# BSR033A.net
KiCad netlist of a schematic drawn in Altium Designer
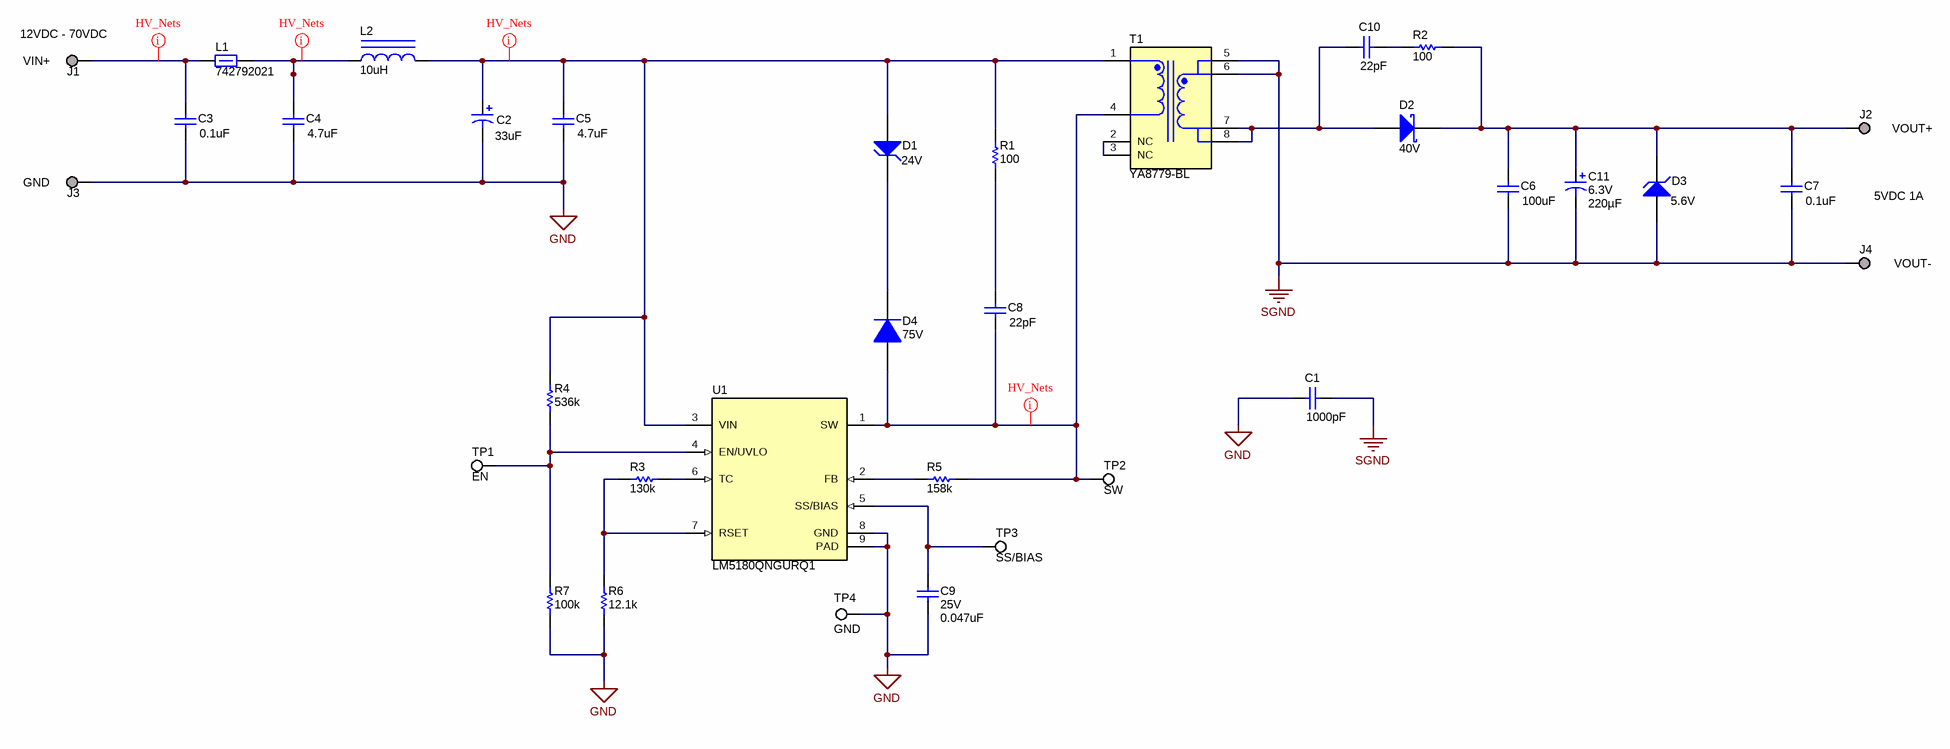
[diagram p0: BSR033A.SchDoc]

(export (version "E")
  (design (tool "Eeschema 10.0.6"))
  (components
    (comp (ref "C1")
      (value "202R18W102KV4E")
      (footprint "1206_190")
      (description "CAP, CERM, 1000 pF, 2000 V, +/- 10%, X7R, 1206_190")
      (fields
        (field (name "MANUFACTURER") "Johanson Technology")
        (field (name "VALUEDISPLAYED") "1000pF")
        (field (name "PUBLISHER") "Texas Instruments")
      )
      (libsource (lib "Altium Vault - TI") (part "CMP-0008572-2"))
    )
    (comp (ref "C2")
      (value "EEE-FK2A330P")
      (footprint "SM_RADIAL_G")
      (description "CAP, AL, 33 uF, 100 V, +/- 20%, 0.7 ohm, AEC-Q200 Grade 2, SMD")
      (fields
        (field (name "MANUFACTURER") "Panasonic")
        (field (name "VALUEDISPLAYED") "33uF")
        (field (name "PUBLISHER") "Texas Instruments")
      )
      (libsource (lib "Altium Vault - TI") (part "CMP-0011203-2"))
    )
    (comp (ref "C3")
      (value "GRM188R72A104KA35J")
      (footprint "0603L")
      (description "CAP, CERM, 0.1 uF, 100 V, +/- 10%, X7R, 0603")
      (fields
        (field (name "MANUFACTURER") "MuRata")
        (field (name "VALUEDISPLAYED") "0.1uF")
        (field (name "PUBLISHER") "Texas Instruments")
      )
      (libsource (lib "Altium Vault - TI") (part "CMP-0007470-5"))
    )
    (comp (ref "C4")
      (value "GRM32DC72A475KE01L")
      (footprint "1210_220")
      (description "CAP, CERM, 4.7 uF, 100 V, +/- 10%, X7S, 1210")
      (fields
        (field (name "MANUFACTURER") "MuRata")
        (field (name "VALUEDISPLAYED") "4.7uF")
        (field (name "PUBLISHER") "Texas Instruments")
      )
      (libsource (lib "Altium Vault - TI") (part "CMP-0009182-2"))
    )
    (comp (ref "C5")
      (value "GRM32DC72A475KE01L")
      (footprint "1210_220")
      (description "CAP, CERM, 4.7 uF, 100 V, +/- 10%, X7S, 1210")
      (fields
        (field (name "MANUFACTURER") "MuRata")
        (field (name "VALUEDISPLAYED") "4.7uF")
        (field (name "PUBLISHER") "Texas Instruments")
      )
      (libsource (lib "Altium Vault - TI") (part "CMP-0009182-2"))
    )
    (comp (ref "C6")
      (value "GRM32EC80J107ME20L")
      (footprint "1210_270")
      (description "CAP, CERM, 100 uF, 6.3 V, +/- 20%, X6S, 1210")
      (fields
        (field (name "MANUFACTURER") "MuRata")
        (field (name "VALUEDISPLAYED") "100uF")
        (field (name "PUBLISHER") "Texas Instruments")
      )
      (libsource (lib "Altium Vault - TI") (part "Capacitor"))
    )
    (comp (ref "C7")
      (value "GRM188R72A104KA35J")
      (footprint "0603L")
      (description "CAP, CERM, 0.1 uF, 100 V, +/- 10%, X7R, 0603")
      (fields
        (field (name "MANUFACTURER") "MuRata")
        (field (name "VALUEDISPLAYED") "0.1uF")
        (field (name "PUBLISHER") "Texas Instruments")
      )
      (libsource (lib "Altium Vault - TI") (part "CMP-0007470-5"))
    )
    (comp (ref "C8")
      (value "GRM1885C2A220JA01D")
      (footprint "0603_HV")
      (description "CAP, CERM, 22 pF, 100 V, +/- 5%, C0G/NP0, 0603")
      (fields
        (field (name "MANUFACTURER") "MuRata")
        (field (name "VALUEDISPLAYED") "22pF")
        (field (name "PUBLISHER") "Texas Instruments")
      )
      (libsource (lib "Altium Vault - TI") (part "CMP-0007255-4"))
    )
    (comp (ref "C9")
      (value "GCM188R71E473KA37D")
      (footprint "0603L")
      (description "CAP, CERM, 0.047 uF, 25 V, +/- 10%, X7R, AEC-Q200 Grade 1, 0603")
      (fields
        (field (name "MANUFACTURER") "MuRata")
        (field (name "VDC_V") "25V")
        (field (name "VALUEDISPLAYED") "0.047uF")
        (field (name "PUBLISHER") "Texas Instruments")
      )
      (libsource (lib "Altium Vault - TI") (part "CMP-0007141-5"))
    )
    (comp (ref "C10")
      (value "GRM1885C2A220JA01D")
      (footprint "0603_HV")
      (description "CAP, CERM, 22 pF, 100 V, +/- 5%, C0G/NP0, 0603")
      (fields
        (field (name "MANUFACTURER") "MuRata")
        (field (name "VALUEDISPLAYED") "22pF")
        (field (name "PUBLISHER") "Texas Instruments")
      )
      (libsource (lib "Altium Vault - TI") (part "CMP-0007255-4"))
    )
    (comp (ref "C11")
      (value "T598D107M010ATE025")
      (footprint "7343-31")
      (description "CAP, Aluminum Polymer, 220 µF, 6.3 V,+/- 20%, 0.01 ohm, 7343-31 SMD")
      (fields
        (field (name "MANUFACTURER") "MuRata")
        (field (name "PARTNUMBER") "ECASD60J227M010K00")
        (field (name "VDC_V") "6.3V")
        (field (name "VALUEDISPLAYED") "220µF")
      )
      (libsource (lib "Altium Vault - TI") (part "Cap_Polarized"))
    )
    (comp (ref "D1")
      (value "DFLZ24-7")
      (footprint "PowerDI123")
      (description "Diode, Zener, 24 V, 1 W, PowerDI123")
      (fields
        (field (name "VZ_V") "24V")
        (field (name "MANUFACTURER") "Diodes Inc.")
        (field (name "PUBLISHER") "Texas Instruments")
      )
      (libsource (lib "Altium Vault - TI") (part "CMP-0005415-2"))
    )
    (comp (ref "D2")
      (value "40V")
      (footprint "SMAF")
      (description "Diode, Schottky, 40 V, 3 A, AEC-Q101, SMAF")
      (fields
        (field (name "PARTNUMBER") "FSV340AF")
        (field (name "MANUFACTURER") "Fairchild Semiconductor")
        (field (name "PUBLISHER") "Texas Instruments")
      )
      (libsource (lib "Altium Vault - TI") (part "CMP-0028855-1"))
    )
    (comp (ref "D3")
      (value "MMSZ5232BS-7-F")
      (footprint "SOD-323")
      (description "Diode, Zener, 5.6 V, 200 mW, SOD-323")
      (fields
        (field (name "VZ_V") "5.6V")
        (field (name "MANUFACTURER") "Diodes Inc.")
        (field (name "PUBLISHER") "Texas Instruments")
      )
      (libsource (lib "Altium Vault - TI") (part "CMP-0005855-1"))
    )
    (comp (ref "D4")
      (value "75V")
      (footprint "SOD-323")
      (description "Diode, Ultrafast, 75 V, 0.25 A, SOD-323")
      (fields
        (field (name "MANUFACTURER") "Central Semiconductor")
        (field (name "PARTNUMBER") "CMDD4448")
        (field (name "PUBLISHER") "Texas Instruments")
      )
      (libsource (lib "Altium Vault - TI") (part "CMP-0029019-1"))
    )
    (comp (ref "J1")
      (value "1573-2")
      (footprint "Keystone1573-2")
      (description "Terminal, Turret, TH, Double")
      (fields (field (name "MANUFACTURER") "Keystone") (field (name "PUBLISHER") "Texas Instruments"))
      (libsource (lib "Altium Vault - TI") (part "CMP-0055119-1"))
    )
    (comp (ref "J2")
      (value "1573-2")
      (footprint "Keystone1573-2")
      (description "Terminal, Turret, TH, Double")
      (fields (field (name "MANUFACTURER") "Keystone") (field (name "PUBLISHER") "Texas Instruments"))
      (libsource (lib "Altium Vault - TI") (part "CMP-0055119-1"))
    )
    (comp (ref "J3")
      (value "1573-2")
      (footprint "Keystone1573-2")
      (description "Terminal, Turret, TH, Double")
      (fields (field (name "MANUFACTURER") "Keystone") (field (name "PUBLISHER") "Texas Instruments"))
      (libsource (lib "Altium Vault - TI") (part "Turret"))
    )
    (comp (ref "J4")
      (value "1573-2")
      (footprint "Keystone1573-2")
      (description "Terminal, Turret, TH, Double")
      (fields (field (name "MANUFACTURER") "Keystone") (field (name "PUBLISHER") "Texas Instruments"))
      (libsource (lib "Altium Vault - TI") (part "Turret"))
    )
    (comp (ref "L1")
      (value "742792021")
      (footprint "0805_HV")
      (description "Ferrite Bead, 22 ohm @ 100 MHz, 6 A, 0805")
      (fields (field (name "MANUFACTURER") "Wurth Elektronik") (field (name "PUBLISHER") "Texas Instruments"))
      (libsource (lib "Altium Vault - TI") (part "Ferrite_Bead"))
    )
    (comp (ref "L2")
      (value "744042100")
      (footprint "WE-TPC-M1")
      (description "Inductor, Shielded Drum Core, Ferrite, 10 uH, 1 A, 0.12 ohm, SMD")
      (fields
        (field (name "MANUFACTURER") "Wurth Elektronik")
        (field (name "VALUEDISPLAYED") "10uH")
        (field (name "PUBLISHER") "Texas Instruments")
      )
      (libsource (lib "Altium Vault - TI") (part "CMP-0063804-1"))
    )
    (comp (ref "R1")
      (value "CRCW0603100RFKEA")
      (footprint "0603L")
      (description "RES, 100, 1%, 0.1 W, 0603")
      (fields
        (field (name "MANUFACTURER") "Vishay-Dale")
        (field (name "VALUEDISPLAYED") "100")
        (field (name "PUBLISHER") "Texas Instruments")
      )
      (libsource (lib "Altium Vault - TI") (part "CMP-0021991-3"))
    )
    (comp (ref "R2")
      (value "CRCW0603100RFKEA")
      (footprint "0603L")
      (description "RES, 100, 1%, 0.1 W, 0603")
      (fields
        (field (name "MANUFACTURER") "Vishay-Dale")
        (field (name "VALUEDISPLAYED") "100")
        (field (name "PUBLISHER") "Texas Instruments")
      )
      (libsource (lib "Altium Vault - TI") (part "CMP-0021991-3"))
    )
    (comp (ref "R3")
      (value "CRCW0603130KFKEA")
      (footprint "0603L")
      (description "RES, 130 k, 1%, 0.1 W, AEC-Q200 Grade 0, 0603")
      (fields (field (name "MANUFACTURER") "Vishay-Dale") (field (name "VALUEDISPLAYED") "130k"))
      (libsource (lib "Altium Vault - TI") (part "CMP-0022036-4"))
    )
    (comp (ref "R4")
      (value "CRCW0603536KFKEA")
      (footprint "0603_HV")
      (description "RES, 536 k, 1%, 0.1 W, AEC-Q200 Grade 0, 0603")
      (fields (field (name "MANUFACTURER") "Vishay-Dale") (field (name "VALUEDISPLAYED") "536k"))
      (libsource (lib "Altium Vault - TI") (part "CMP-0022488-4"))
    )
    (comp (ref "R5")
      (value "CRCW0603158KFKEA")
      (footprint "0603_HV")
      (description "RES, 158 k, 1%, 0.1 W, AEC-Q200 Grade 0, 0603")
      (fields (field (name "MANUFACTURER") "Vishay-Dale") (field (name "VALUEDISPLAYED") "158k"))
      (libsource (lib "Altium Vault - TI") (part "CMP-0022064-4"))
    )
    (comp (ref "R6")
      (value "CRCW060312K1FKEA")
      (footprint "0603L")
      (description "RES, 12.1 k, 1%, 0.1 W, 0603")
      (fields
        (field (name "MANUFACTURER") "Vishay-Dale")
        (field (name "VALUEDISPLAYED") "12.1k")
        (field (name "PUBLISHER") "Texas Instruments")
      )
      (libsource (lib "Altium Vault - TI") (part "CMP-0022030-3"))
    )
    (comp (ref "R7")
      (value "CRCW0603100KFKEA")
      (footprint "0603L")
      (description "RES, 100 k, 1%, 0.1 W, AEC-Q200 Grade 0, 0603")
      (fields (field (name "MANUFACTURER") "Vishay-Dale") (field (name "VALUEDISPLAYED") "100k"))
      (libsource (lib "Altium Vault - TI") (part "CMP-0021990-4"))
    )
    (comp (ref "T1")
      (value "YA8779-BL")
      (footprint "Coilcraft_YA8779-CL")
      (description "Transformer, 30 uH, SMD")
      (fields (field (name "MANUFACTURER") "Coilcraft"))
      (libsource (lib "Altium Vault - TI") (part "Coilcraft_YA8779-CL"))
    )
    (comp (ref "TP1")
      (value "EN")
      (footprint "Testpoint_Keystone_Miniature")
      (description "Test Point, Miniature, SMT")
      (fields
        (field (name "MANUFACTURER") "Keystone")
        (field (name "PARTNUMBER") "5015")
        (field (name "PUBLISHER") "Texas Instruments")
      )
      (libsource (lib "Altium Vault - TI") (part "CMP-0055152-1"))
    )
    (comp (ref "TP2")
      (value "SW")
      (footprint "Testpoint_Keystone_Miniature")
      (description "Test Point, Miniature, SMT")
      (fields
        (field (name "MANUFACTURER") "Keystone")
        (field (name "PARTNUMBER") "5015")
        (field (name "PUBLISHER") "Texas Instruments")
      )
      (libsource (lib "Altium Vault - TI") (part "CMP-0055152-1"))
    )
    (comp (ref "TP3")
      (value "SS/BIAS")
      (footprint "Testpoint_Keystone_Miniature")
      (description "Test Point, Miniature, SMT")
      (fields
        (field (name "MANUFACTURER") "Keystone")
        (field (name "PARTNUMBER") "5015")
        (field (name "PUBLISHER") "Texas Instruments")
      )
      (libsource (lib "Altium Vault - TI") (part "CMP-0055152-1"))
    )
    (comp (ref "TP4")
      (value "GND")
      (footprint "Testpoint_Keystone_Miniature")
      (description "Test Point, Miniature, SMT")
      (fields
        (field (name "MANUFACTURER") "Keystone")
        (field (name "PARTNUMBER") "5015")
        (field (name "PUBLISHER") "Texas Instruments")
      )
      (libsource (lib "Altium Vault - TI") (part "CMP-0055152-1"))
    )
    (comp (ref "U1")
      (value "LM5180QNGURQ1")
      (footprint "NGU0008C")
      (description "70-V PSR Flyback Converter With 100-V, 1.2-A Power Switch and Ultra-Low IQ, NGU0008C (WSON-8)")
      (fields
        (field (name "ALTERNATE PARTNUMBER") "LM5180QNGUTQ1")
        (field (name "MANUFACTURER") "Texas Instruments")
        (field (name "PARTNUMBER") "LM5180QNGURQ1")
      )
      (libsource (lib "Altium Vault - TI") (part "LM5180-Q1"))
    )
  )
  (nets
    (net (code "1") (name "GND") (class "Default")
      (node (ref "C1") (pin "2") (pinfunction "2_2") (pintype "passive"))
      (node (ref "C2") (pin "2") (pinfunction "-_2") (pintype "passive"))
      (node (ref "C3") (pin "2") (pinfunction "2_2") (pintype "passive"))
      (node (ref "C4") (pin "1") (pinfunction "1_1") (pintype "passive"))
      (node (ref "C5") (pin "1") (pinfunction "1_1") (pintype "passive"))
      (node (ref "C9") (pin "2") (pinfunction "2_2") (pintype "passive"))
      (node (ref "J3") (pin "1") (pintype "passive"))
      (node (ref "R6") (pin "1") (pinfunction "1_1") (pintype "passive"))
      (node (ref "R7") (pin "1") (pinfunction "1_1") (pintype "passive"))
      (node (ref "TP4") (pin "1") (pintype "passive"))
      (node (ref "U1") (pin "8") (pinfunction "GND_8") (pintype "power_in"))
      (node (ref "U1") (pin "9") (pinfunction "PAD_9") (pintype "power_in"))
    )
    (net (code "2") (name "Net-(C2-+)") (class "Default")
      (node (ref "C2") (pin "1") (pinfunction "+_1") (pintype "passive"))
      (node (ref "C5") (pin "2") (pinfunction "2_2") (pintype "passive"))
      (node (ref "D1") (pin "2") (pinfunction "A_2") (pintype "passive"))
      (node (ref "L2") (pin "2") (pinfunction "2_2") (pintype "passive"))
      (node (ref "R1") (pin "2") (pinfunction "2_2") (pintype "passive"))
      (node (ref "R4") (pin "2") (pinfunction "2_2") (pintype "passive"))
      (node (ref "T1") (pin "1") (pinfunction "1_1") (pintype "passive"))
      (node (ref "U1") (pin "3") (pinfunction "VIN_3") (pintype "power_in"))
    )
    (net (code "3") (name "Net-(C3-Pad1)") (class "Default")
      (node (ref "C3") (pin "1") (pinfunction "1_1") (pintype "passive"))
      (node (ref "J1") (pin "1") (pintype "passive"))
      (node (ref "L1") (pin "1") (pinfunction "1_1") (pintype "passive"))
    )
    (net (code "4") (name "Net-(C4-Pad2)") (class "Default")
      (node (ref "C4") (pin "2") (pinfunction "2_2") (pintype "passive"))
      (node (ref "L1") (pin "2") (pinfunction "2_2") (pintype "passive"))
      (node (ref "L2") (pin "1") (pinfunction "1_1") (pintype "passive"))
    )
    (net (code "5") (name "Net-(C8-Pad1)") (class "Default")
      (node (ref "C8") (pin "1") (pinfunction "1_1") (pintype "passive"))
      (node (ref "R1") (pin "1") (pinfunction "1_1") (pintype "passive"))
    )
    (net (code "6") (name "Net-(C10-Pad1)") (class "Default")
      (node (ref "C10") (pin "1") (pinfunction "1_1") (pintype "passive"))
      (node (ref "R2") (pin "2") (pinfunction "2_2") (pintype "passive"))
    )
    (net (code "7") (name "Net-(C11-+)") (class "Default")
      (node (ref "C11") (pin "1") (pinfunction "+_1") (pintype "passive"))
      (node (ref "C6") (pin "1") (pinfunction "1_1") (pintype "passive"))
      (node (ref "C7") (pin "1") (pinfunction "1_1") (pintype "passive"))
      (node (ref "D2") (pin "1") (pinfunction "K_1") (pintype "passive"))
      (node (ref "D3") (pin "1") (pinfunction "K_1") (pintype "passive"))
      (node (ref "J2") (pin "1") (pintype "passive"))
      (node (ref "R2") (pin "1") (pinfunction "1_1") (pintype "passive"))
    )
    (net (code "8") (name "Net-(D1-K)") (class "Default")
      (node (ref "D1") (pin "1") (pinfunction "K_1") (pintype "passive"))
      (node (ref "D4") (pin "1") (pinfunction "K_1") (pintype "passive"))
    )
    (net (code "9") (name "Net-(D2-A)") (class "Default")
      (node (ref "C10") (pin "2") (pinfunction "2_2") (pintype "passive"))
      (node (ref "D2") (pin "2") (pinfunction "A_2") (pintype "passive"))
      (node (ref "T1") (pin "7") (pinfunction "7_7") (pintype "passive"))
      (node (ref "T1") (pin "8") (pinfunction "8_8") (pintype "passive"))
    )
    (net (code "10") (name "Net-(D4-A)") (class "Default")
      (node (ref "C8") (pin "2") (pinfunction "2_2") (pintype "passive"))
      (node (ref "D4") (pin "2") (pinfunction "A_2") (pintype "passive"))
      (node (ref "R5") (pin "2") (pinfunction "2_2") (pintype "passive"))
      (node (ref "T1") (pin "4") (pinfunction "4_4") (pintype "passive"))
      (node (ref "TP2") (pin "1") (pintype "passive"))
      (node (ref "U1") (pin "1") (pinfunction "SW_1") (pintype "power_in"))
    )
    (net (code "11") (name "Net-(T1-NC-Pad2)") (class "Default")
      (node (ref "T1") (pin "2") (pinfunction "NC_2") (pintype "passive"))
      (node (ref "T1") (pin "3") (pinfunction "NC_3") (pintype "passive"))
    )
    (net (code "12") (name "Net-(U1-EN{slash}UVLO)") (class "Default")
      (node (ref "R4") (pin "1") (pinfunction "1_1") (pintype "passive"))
      (node (ref "R7") (pin "2") (pinfunction "2_2") (pintype "passive"))
      (node (ref "TP1") (pin "1") (pintype "passive"))
      (node (ref "U1") (pin "4") (pinfunction "EN/UVLO_4") (pintype "input"))
    )
    (net (code "13") (name "Net-(U1-FB)") (class "Default")
      (node (ref "R5") (pin "1") (pinfunction "1_1") (pintype "passive"))
      (node (ref "U1") (pin "2") (pinfunction "FB_2") (pintype "input"))
    )
    (net (code "14") (name "Net-(U1-RSET)") (class "Default")
      (node (ref "R3") (pin "1") (pinfunction "1_1") (pintype "passive"))
      (node (ref "R6") (pin "2") (pinfunction "2_2") (pintype "passive"))
      (node (ref "U1") (pin "7") (pinfunction "RSET_7") (pintype "input"))
    )
    (net (code "15") (name "Net-(U1-SS{slash}BIAS)") (class "Default")
      (node (ref "C9") (pin "1") (pinfunction "1_1") (pintype "passive"))
      (node (ref "TP3") (pin "1") (pintype "passive"))
      (node (ref "U1") (pin "5") (pinfunction "SS/BIAS_5") (pintype "input"))
    )
    (net (code "16") (name "Net-(U1-TC)") (class "Default")
      (node (ref "R3") (pin "2") (pinfunction "2_2") (pintype "passive"))
      (node (ref "U1") (pin "6") (pinfunction "TC_6") (pintype "input"))
    )
    (net (code "17") (name "SGND") (class "Default")
      (node (ref "C1") (pin "1") (pinfunction "1_1") (pintype "passive"))
      (node (ref "C11") (pin "2") (pinfunction "-_2") (pintype "passive"))
      (node (ref "C6") (pin "2") (pinfunction "2_2") (pintype "passive"))
      (node (ref "C7") (pin "2") (pinfunction "2_2") (pintype "passive"))
      (node (ref "D3") (pin "2") (pinfunction "A_2") (pintype "passive"))
      (node (ref "J4") (pin "1") (pintype "passive"))
      (node (ref "T1") (pin "5") (pinfunction "5_5") (pintype "passive"))
      (node (ref "T1") (pin "6") (pinfunction "6_6") (pintype "passive"))
    )
  )
)
